# carte_pui.net
KiCad netlist of a schematic drawn in EAGLE
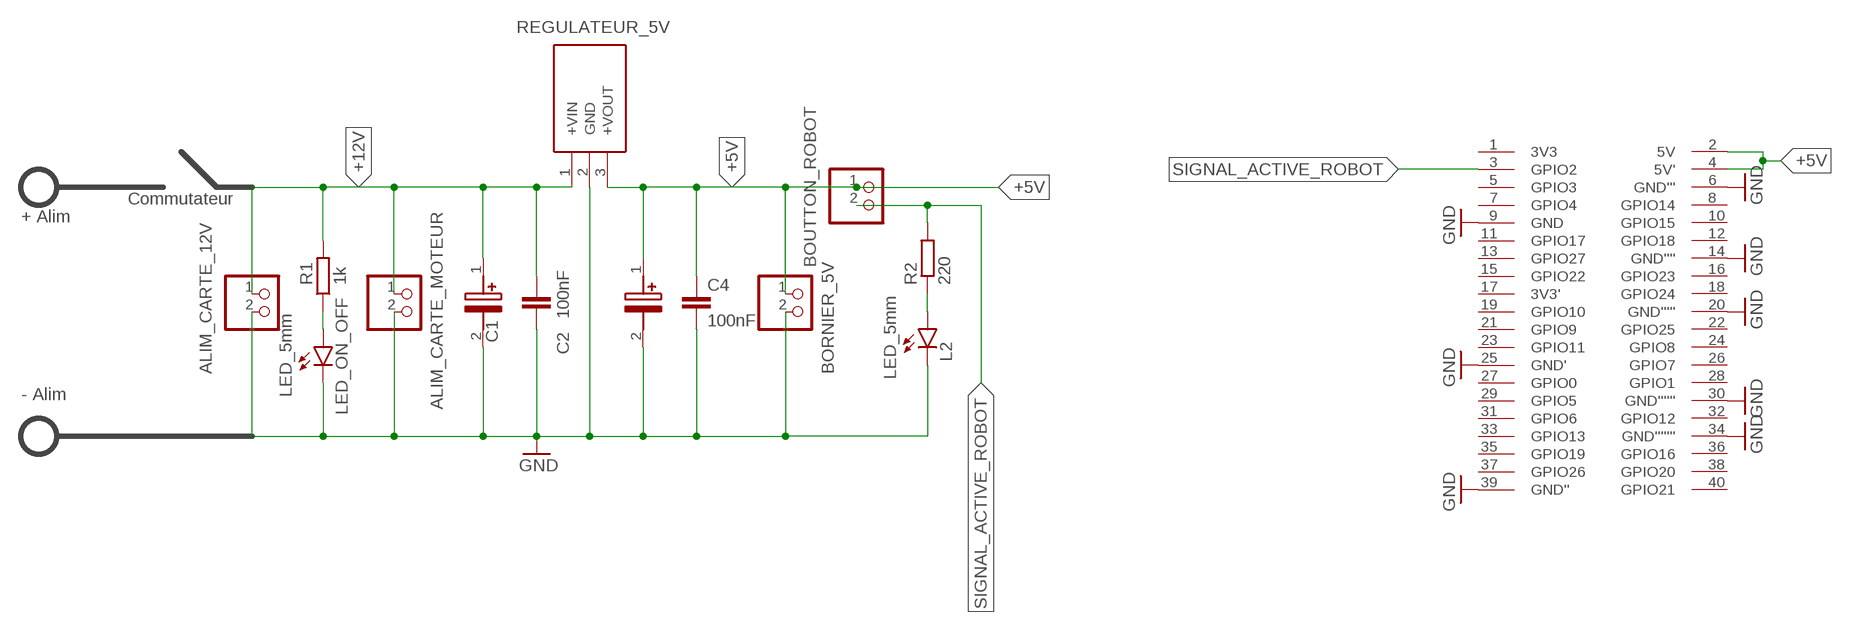
[diagram p0: schematic, sheet 1]

(export (version "E")
  (design (tool "Eeschema 10.0.6"))
  (components
    (comp (ref "ALIM_CARTE_12V")
      (value "BORNIER_2_ROND_LARGE")
      (footprint "eagle-import:BORNIER_2_ROND_LARGE")
      (libsource (lib "eagle-import") (part "BORNIER_2_ROND_LARGE"))
    )
    (comp (ref "ALIM_CARTE_MOTEUR")
      (value "BORNIER_2_ROND_LARGE")
      (footprint "eagle-import:BORNIER_2_ROND_LARGE")
      (libsource (lib "eagle-import") (part "BORNIER_2_ROND_LARGE"))
    )
    (comp (ref "BORNIER_5V")
      (value "BORNIER_2_ROND_LARGE")
      (footprint "eagle-import:BORNIER_2_ROND_LARGE")
      (libsource (lib "eagle-import") (part "BORNIER_2_ROND_LARGE"))
    )
    (comp (ref "BOUTTON_ROBOT")
      (value "BORNIER_2_ROND_LARGE")
      (footprint "eagle-import:BORNIER_2_ROND_LARGE")
      (libsource (lib "eagle-import") (part "BORNIER_2_ROND_LARGE"))
    )
    (comp (ref "C1")
      (value "10uF")
      (footprint "eagle-import:CAPPRD350W65D800H1300")
      (fields
        (field (name "MANUFACTURER_PART_NUMBER") "EEU-FR1C471B")
        (field (name "MOUSER_PART_NUMBER") "667-EEU-FR1C471B")
      )
      (libsource (lib "eagle-import") (part "EEU-FR1C471B"))
    )
    (comp (ref "C2")
      (value "100nF")
      (footprint "eagle-import:C050-030X040")
      (libsource (lib "eagle-import") (part "CERAMIC_CAPACITOR"))
    )
    (comp (ref "C3")
      (value "10uF")
      (footprint "eagle-import:CAPPRD350W65D800H1300")
      (fields
        (field (name "MANUFACTURER_PART_NUMBER") "EEU-FR1C471B")
        (field (name "MOUSER_PART_NUMBER") "667-EEU-FR1C471B")
      )
      (libsource (lib "eagle-import") (part "EEU-FR1C471B"))
    )
    (comp (ref "C4")
      (value "100nF")
      (footprint "eagle-import:C050-030X040")
      (libsource (lib "eagle-import") (part "CERAMIC_CAPACITOR"))
    )
    (comp (ref "L2")
      (value "LED_5mm")
      (footprint "eagle-import:LED5MM")
      (libsource (lib "eagle-import") (part "LED5MM"))
    )
    (comp (ref "LED_ON_OFF")
      (value "LED_5mm")
      (footprint "eagle-import:LED5MM")
      (libsource (lib "eagle-import") (part "LED5MM"))
    )
    (comp (ref "R1")
      (value "1k")
      (footprint "eagle-import:0207_7-90")
      (libsource (lib "eagle-import") (part "RESISTOR_1/4W90PAD"))
    )
    (comp (ref "R2")
      (value "220")
      (footprint "eagle-import:0207_7-90")
      (libsource (lib "eagle-import") (part "RESISTOR_1/4W90PAD"))
    )
    (comp (ref "REGULATEUR_5V")
      (value "TSR_2-2450")
      (footprint "eagle-import:TSR-2")
      (fields
        (field (name "MANUFACTURER_PART_NUMBER") "TSR 2-2450")
        (field (name "MOUSER_PART_NUMBER") "495-TSR2-2450")
      )
      (libsource (lib "eagle-import") (part "TSR_2-2450"))
    )
    (comp (ref "U$1")
      (value "PI4")
      (footprint "eagle-import:PI4")
      (libsource (lib "eagle-import") (part "PI4"))
    )
  )
  (nets
    (net (code "1") (name "+5V") (class "Default")
      (node (ref "BORNIER_5V") (pin "1") (pinfunction "1_1") (pintype "passive"))
      (node (ref "BOUTTON_ROBOT") (pin "1") (pinfunction "1_1") (pintype "passive"))
      (node (ref "C3") (pin "1") (pinfunction "+_1") (pintype "bidirectional"))
      (node (ref "C4") (pin "1") (pinfunction "1_1") (pintype "passive"))
      (node (ref "REGULATEUR_5V") (pin "3") (pinfunction "+VOUT_3") (pintype "output"))
      (node (ref "U$1") (pin "2") (pinfunction "5V_2") (pintype "bidirectional"))
      (node (ref "U$1") (pin "4") (pinfunction "5V'_4") (pintype "bidirectional"))
    )
    (net (code "2") (name "+12V") (class "Default")
      (node (ref "ALIM_CARTE_12V") (pin "1") (pinfunction "1_1") (pintype "passive"))
      (node (ref "ALIM_CARTE_MOTEUR") (pin "1") (pinfunction "1_1") (pintype "passive"))
      (node (ref "C1") (pin "1") (pinfunction "+_1") (pintype "bidirectional"))
      (node (ref "C2") (pin "1") (pinfunction "1_1") (pintype "passive"))
      (node (ref "R1") (pin "2") (pinfunction "2_2") (pintype "passive"))
      (node (ref "REGULATEUR_5V") (pin "1") (pinfunction "+VIN_1") (pintype "input"))
    )
    (net (code "3") (name "GND") (class "Default")
      (node (ref "ALIM_CARTE_12V") (pin "2") (pinfunction "2_2") (pintype "passive"))
      (node (ref "ALIM_CARTE_MOTEUR") (pin "2") (pinfunction "2_2") (pintype "passive"))
      (node (ref "BORNIER_5V") (pin "2") (pinfunction "2_2") (pintype "passive"))
      (node (ref "C1") (pin "2") (pinfunction "-_2") (pintype "bidirectional"))
      (node (ref "C2") (pin "2") (pinfunction "2_2") (pintype "passive"))
      (node (ref "C3") (pin "2") (pinfunction "-_2") (pintype "bidirectional"))
      (node (ref "C4") (pin "2") (pinfunction "2_2") (pintype "passive"))
      (node (ref "L2") (pin "K") (pinfunction "C_K") (pintype "passive"))
      (node (ref "LED_ON_OFF") (pin "K") (pinfunction "C_K") (pintype "passive"))
      (node (ref "REGULATEUR_5V") (pin "2") (pinfunction "GND_2") (pintype "power_in"))
      (node (ref "U$1") (pin "14") (pinfunction "GND''''_14") (pintype "bidirectional"))
      (node (ref "U$1") (pin "20") (pinfunction "GND'''''_20") (pintype "bidirectional"))
      (node (ref "U$1") (pin "25") (pinfunction "GND'_25") (pintype "bidirectional"))
      (node (ref "U$1") (pin "30") (pinfunction "GND''''''_30") (pintype "bidirectional"))
      (node (ref "U$1") (pin "34") (pinfunction "GND'''''''_34") (pintype "bidirectional"))
      (node (ref "U$1") (pin "39") (pinfunction "GND''_39") (pintype "bidirectional"))
      (node (ref "U$1") (pin "6") (pinfunction "GND'''_6") (pintype "bidirectional"))
      (node (ref "U$1") (pin "9") (pinfunction "GND_9") (pintype "bidirectional"))
    )
    (net (code "4") (name "Net-(L2-PadA)") (class "Default")
      (node (ref "L2") (pin "A") (pinfunction "A_A") (pintype "passive"))
      (node (ref "R2") (pin "1") (pinfunction "1_1") (pintype "passive"))
    )
    (net (code "5") (name "Net-(LED_ON_OFF-PadA)") (class "Default")
      (node (ref "LED_ON_OFF") (pin "A") (pinfunction "A_A") (pintype "passive"))
      (node (ref "R1") (pin "1") (pinfunction "1_1") (pintype "passive"))
    )
    (net (code "6") (name "SIGNAL_ACTIVE_ROBOT") (class "Default")
      (node (ref "BOUTTON_ROBOT") (pin "2") (pinfunction "2_2") (pintype "passive"))
      (node (ref "R2") (pin "2") (pinfunction "2_2") (pintype "passive"))
      (node (ref "U$1") (pin "3") (pinfunction "GPIO2_3") (pintype "bidirectional"))
    )
    (net (code "7") (name "unconnected-(U$1-3V3'-Pad17)") (class "Default")
      (node (ref "U$1") (pin "17") (pinfunction "3V3'_17") (pintype "bidirectional"))
    )
    (net (code "8") (name "unconnected-(U$1-3V3-Pad1)") (class "Default")
      (node (ref "U$1") (pin "1") (pinfunction "3V3_1") (pintype "bidirectional"))
    )
    (net (code "9") (name "unconnected-(U$1-GPIO0-Pad27)") (class "Default")
      (node (ref "U$1") (pin "27") (pinfunction "GPIO0_27") (pintype "bidirectional"))
    )
    (net (code "10") (name "unconnected-(U$1-GPIO1-Pad28)") (class "Default")
      (node (ref "U$1") (pin "28") (pinfunction "GPIO1_28") (pintype "bidirectional"))
    )
    (net (code "11") (name "unconnected-(U$1-GPIO3-Pad5)") (class "Default")
      (node (ref "U$1") (pin "5") (pinfunction "GPIO3_5") (pintype "bidirectional"))
    )
    (net (code "12") (name "unconnected-(U$1-GPIO4-Pad7)") (class "Default")
      (node (ref "U$1") (pin "7") (pinfunction "GPIO4_7") (pintype "bidirectional"))
    )
    (net (code "13") (name "unconnected-(U$1-GPIO5-Pad29)") (class "Default")
      (node (ref "U$1") (pin "29") (pinfunction "GPIO5_29") (pintype "bidirectional"))
    )
    (net (code "14") (name "unconnected-(U$1-GPIO6-Pad31)") (class "Default")
      (node (ref "U$1") (pin "31") (pinfunction "GPIO6_31") (pintype "bidirectional"))
    )
    (net (code "15") (name "unconnected-(U$1-GPIO7-Pad26)") (class "Default")
      (node (ref "U$1") (pin "26") (pinfunction "GPIO7_26") (pintype "bidirectional"))
    )
    (net (code "16") (name "unconnected-(U$1-GPIO8-Pad24)") (class "Default")
      (node (ref "U$1") (pin "24") (pinfunction "GPIO8_24") (pintype "bidirectional"))
    )
    (net (code "17") (name "unconnected-(U$1-GPIO9-Pad21)") (class "Default")
      (node (ref "U$1") (pin "21") (pinfunction "GPIO9_21") (pintype "bidirectional"))
    )
    (net (code "18") (name "unconnected-(U$1-GPIO10-Pad19)") (class "Default")
      (node (ref "U$1") (pin "19") (pinfunction "GPIO10_19") (pintype "bidirectional"))
    )
    (net (code "19") (name "unconnected-(U$1-GPIO11-Pad23)") (class "Default")
      (node (ref "U$1") (pin "23") (pinfunction "GPIO11_23") (pintype "bidirectional"))
    )
    (net (code "20") (name "unconnected-(U$1-GPIO12-Pad32)") (class "Default")
      (node (ref "U$1") (pin "32") (pinfunction "GPIO12_32") (pintype "bidirectional"))
    )
    (net (code "21") (name "unconnected-(U$1-GPIO13-Pad33)") (class "Default")
      (node (ref "U$1") (pin "33") (pinfunction "GPIO13_33") (pintype "bidirectional"))
    )
    (net (code "22") (name "unconnected-(U$1-GPIO14-Pad8)") (class "Default")
      (node (ref "U$1") (pin "8") (pinfunction "GPIO14_8") (pintype "bidirectional"))
    )
    (net (code "23") (name "unconnected-(U$1-GPIO15-Pad10)") (class "Default")
      (node (ref "U$1") (pin "10") (pinfunction "GPIO15_10") (pintype "bidirectional"))
    )
    (net (code "24") (name "unconnected-(U$1-GPIO16-Pad36)") (class "Default")
      (node (ref "U$1") (pin "36") (pinfunction "GPIO16_36") (pintype "bidirectional"))
    )
    (net (code "25") (name "unconnected-(U$1-GPIO17-Pad11)") (class "Default")
      (node (ref "U$1") (pin "11") (pinfunction "GPIO17_11") (pintype "bidirectional"))
    )
    (net (code "26") (name "unconnected-(U$1-GPIO18-Pad12)") (class "Default")
      (node (ref "U$1") (pin "12") (pinfunction "GPIO18_12") (pintype "bidirectional"))
    )
    (net (code "27") (name "unconnected-(U$1-GPIO19-Pad35)") (class "Default")
      (node (ref "U$1") (pin "35") (pinfunction "GPIO19_35") (pintype "bidirectional"))
    )
    (net (code "28") (name "unconnected-(U$1-GPIO20-Pad38)") (class "Default")
      (node (ref "U$1") (pin "38") (pinfunction "GPIO20_38") (pintype "bidirectional"))
    )
    (net (code "29") (name "unconnected-(U$1-GPIO21-Pad40)") (class "Default")
      (node (ref "U$1") (pin "40") (pinfunction "GPIO21_40") (pintype "bidirectional"))
    )
    (net (code "30") (name "unconnected-(U$1-GPIO22-Pad15)") (class "Default")
      (node (ref "U$1") (pin "15") (pinfunction "GPIO22_15") (pintype "bidirectional"))
    )
    (net (code "31") (name "unconnected-(U$1-GPIO23-Pad16)") (class "Default")
      (node (ref "U$1") (pin "16") (pinfunction "GPIO23_16") (pintype "bidirectional"))
    )
    (net (code "32") (name "unconnected-(U$1-GPIO24-Pad18)") (class "Default")
      (node (ref "U$1") (pin "18") (pinfunction "GPIO24_18") (pintype "bidirectional"))
    )
    (net (code "33") (name "unconnected-(U$1-GPIO25-Pad22)") (class "Default")
      (node (ref "U$1") (pin "22") (pinfunction "GPIO25_22") (pintype "bidirectional"))
    )
    (net (code "34") (name "unconnected-(U$1-GPIO26-Pad37)") (class "Default")
      (node (ref "U$1") (pin "37") (pinfunction "GPIO26_37") (pintype "bidirectional"))
    )
    (net (code "35") (name "unconnected-(U$1-GPIO27-Pad13)") (class "Default")
      (node (ref "U$1") (pin "13") (pinfunction "GPIO27_13") (pintype "bidirectional"))
    )
  )
)
